# ESP32.net
KiCad netlist of a schematic drawn in Altium Designer
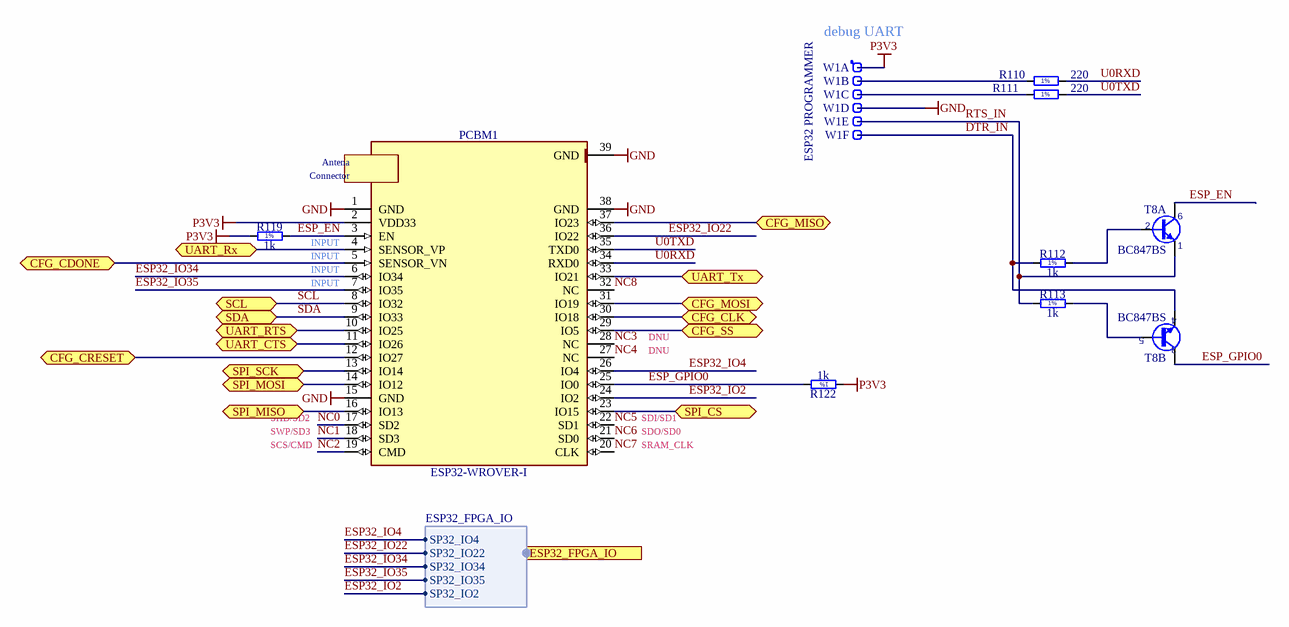
[diagram p0: ESP32.SchDoc]

(export (version "E")
  (design (tool "Eeschema 10.0.6"))
  (components
    (comp (ref "PCBM1")
      (value "ESP32-WROVER-I")
      (footprint "PCBM_ESP32-WROVER-I")
      (description "Generic WiFi-BT-BLE MCU Module")
      (fields
        (field (name "PART NUMBER") "PCBM_ESP32-WROVER-I")
        (field (name "MANUFACTURER") "ESPRESSIF")
        (field (name "AUTHOR") "CERN DEM JLC")
      )
      (libsource (lib "ICs And Semiconductors") (part "PCBM_ESP32-WROVER-I"))
    )
    (comp (ref "R110")
      (value "220")
      (footprint "RESC1005X40N")
      (description "Resistor - 1%")
      (fields
        (field (name "PART NUMBER") "R0402_220R_1%_0.0625W_100PPM")
        (field (name "POWER") "0.0625W")
        (field (name "AUTHOR") "CERN DEM JLC")
      )
      (libsource (lib "Resistors") (part "Resistor - 1%"))
    )
    (comp (ref "R111")
      (value "220")
      (footprint "RESC1005X40N")
      (description "Resistor - 1%")
      (fields
        (field (name "PART NUMBER") "R0402_220R_1%_0.0625W_100PPM")
        (field (name "POWER") "0.0625W")
        (field (name "AUTHOR") "CERN DEM JLC")
      )
      (libsource (lib "Resistors") (part "Resistor - 1%"))
    )
    (comp (ref "R112")
      (value "1k")
      (footprint "RESC1005X40N")
      (description "Resistor - 1%")
      (fields
        (field (name "PART NUMBER") "R0402_1K_1%_0.0625W_100PPM")
        (field (name "POWER") "0.0625W")
        (field (name "AUTHOR") "CERN DEM JLC")
      )
      (libsource (lib "Resistors") (part "Resistor - 1%"))
    )
    (comp (ref "R113")
      (value "1k")
      (footprint "RESC1005X40N")
      (description "Resistor - 1%")
      (fields
        (field (name "PART NUMBER") "R0402_1K_1%_0.0625W_100PPM")
        (field (name "POWER") "0.0625W")
        (field (name "AUTHOR") "CERN DEM JLC")
      )
      (libsource (lib "Resistors") (part "Resistor - 1%"))
    )
    (comp (ref "R119")
      (value "1k")
      (footprint "RESC1005X40N")
      (description "Resistor - 1%")
      (fields
        (field (name "PART NUMBER") "R0402_1K_1%_0.0625W_100PPM")
        (field (name "POWER") "0.0625W")
        (field (name "AUTHOR") "CERN DEM JLC")
      )
      (libsource (lib "Resistors") (part "Resistor - 1%"))
    )
    (comp (ref "R122")
      (value "1k")
      (footprint "RESC1005X40N")
      (description "Resistor - 1%")
      (fields
        (field (name "PART NUMBER") "R0402_1K_1%_0.0625W_100PPM")
        (field (name "POWER") "0.0625W")
        (field (name "AUTHOR") "CERN DEM JLC")
      )
      (libsource (lib "Resistors") (part "Resistor - 1%"))
    )
    (comp (ref "T8")
      (value "BC847BS")
      (footprint "SOT65P210X110-6N")
      (description "45V 100mA Dual NPN General-Purpose Transistor")
      (fields (field (name "MANUFACTURER") "NXP SEMICONDUCTORS") (field (name "AUTHOR") "CERN DEM JMW"))
      (libsource (lib "") (part "BC847BS_1"))
    )
    (comp (ref "W1")
      (value "Header 6")
      (footprint "SAMTEC_MTLW-106-07-L-S-250")
      (description "6 Mini Wire-Wrap Contact Strip Header")
      (fields
        (field (name "PART NUMBER") "SAMTEC_MTLW-106-07-L-S-250")
        (field (name "MANUFACTURER") "SAMTEC")
        (field (name "AUTHOR") "CERN DEM BC")
      )
      (libsource (lib "Connectors") (part "Wire-Wrap Contact x6"))
    )
  )
  (nets
    (net (code "2") (name "/CFG_CDONE") (class "Default")
      (node (ref "PCBM1") (pin "5") (pinfunction "SENSOR_VN_5") (pintype "input"))
    )
    (net (code "3") (name "/CFG_CLK") (class "Default")
      (node (ref "PCBM1") (pin "30") (pinfunction "IO18_30") (pintype "bidirectional"))
    )
    (net (code "4") (name "/CFG_CRESET") (class "Default")
      (node (ref "PCBM1") (pin "12") (pinfunction "IO27_12") (pintype "bidirectional"))
    )
    (net (code "5") (name "/CFG_MISO") (class "Default")
      (node (ref "PCBM1") (pin "37") (pinfunction "IO23_37") (pintype "bidirectional"))
    )
    (net (code "6") (name "/CFG_MOSI") (class "Default")
      (node (ref "PCBM1") (pin "31") (pinfunction "IO19_31") (pintype "bidirectional"))
    )
    (net (code "7") (name "/CFG_SS") (class "Default")
      (node (ref "PCBM1") (pin "29") (pinfunction "IO5_29") (pintype "bidirectional"))
    )
    (net (code "8") (name "/DTR_IN") (class "Default")
      (node (ref "R112") (pin "1") (pinfunction "1_1") (pintype "passive"))
      (node (ref "T8") (pin "4") (pinfunction "E_4") (pintype "passive"))
      (node (ref "W1") (pin "6") (pinfunction "6_6") (pintype "bidirectional"))
    )
    (net (code "9") (name "/ESP32_IO2") (class "Default")
      (node (ref "PCBM1") (pin "24") (pinfunction "IO2_24") (pintype "bidirectional"))
    )
    (net (code "10") (name "/ESP32_IO4") (class "Default")
      (node (ref "PCBM1") (pin "26") (pinfunction "IO4_26") (pintype "bidirectional"))
    )
    (net (code "11") (name "/ESP32_IO22") (class "Default")
      (node (ref "PCBM1") (pin "36") (pinfunction "IO22_36") (pintype "bidirectional"))
    )
    (net (code "12") (name "/ESP32_IO34") (class "Default")
      (node (ref "PCBM1") (pin "6") (pinfunction "IO34_6") (pintype "bidirectional"))
    )
    (net (code "13") (name "/ESP32_IO35") (class "Default")
      (node (ref "PCBM1") (pin "7") (pinfunction "IO35_7") (pintype "bidirectional"))
    )
    (net (code "14") (name "/ESP_EN") (class "Default")
      (node (ref "PCBM1") (pin "3") (pinfunction "EN_3") (pintype "input"))
      (node (ref "R119") (pin "2") (pinfunction "2_2") (pintype "passive"))
      (node (ref "T8") (pin "6") (pinfunction "C_6") (pintype "passive"))
    )
    (net (code "15") (name "/ESP_GPIO0") (class "Default")
      (node (ref "PCBM1") (pin "25") (pinfunction "IO0_25") (pintype "bidirectional"))
      (node (ref "R122") (pin "2") (pinfunction "2_2") (pintype "passive"))
      (node (ref "T8") (pin "3") (pinfunction "C_3") (pintype "passive"))
    )
    (net (code "16") (name "/NC0") (class "Default")
      (node (ref "PCBM1") (pin "17") (pinfunction "SD2_17") (pintype "bidirectional"))
    )
    (net (code "17") (name "/NC1") (class "Default")
      (node (ref "PCBM1") (pin "18") (pinfunction "SD3_18") (pintype "bidirectional"))
    )
    (net (code "18") (name "/NC2") (class "Default")
      (node (ref "PCBM1") (pin "19") (pinfunction "CMD_19") (pintype "bidirectional"))
    )
    (net (code "19") (name "/NC3") (class "Default")
      (node (ref "PCBM1") (pin "28") (pinfunction "NC_28") (pintype "passive"))
    )
    (net (code "20") (name "/NC4") (class "Default")
      (node (ref "PCBM1") (pin "27") (pinfunction "NC_27") (pintype "passive"))
    )
    (net (code "21") (name "/NC5") (class "Default")
      (node (ref "PCBM1") (pin "22") (pinfunction "SD1_22") (pintype "bidirectional"))
    )
    (net (code "22") (name "/NC6") (class "Default")
      (node (ref "PCBM1") (pin "21") (pinfunction "SD0_21") (pintype "bidirectional"))
    )
    (net (code "23") (name "/NC7") (class "Default")
      (node (ref "PCBM1") (pin "20") (pinfunction "CLK_20") (pintype "bidirectional"))
    )
    (net (code "24") (name "/NC8") (class "Default")
      (node (ref "PCBM1") (pin "32") (pinfunction "NC_32") (pintype "passive"))
    )
    (net (code "25") (name "/RTS_IN") (class "Default")
      (node (ref "R113") (pin "1") (pinfunction "1_1") (pintype "passive"))
      (node (ref "T8") (pin "1") (pinfunction "E_1") (pintype "passive"))
      (node (ref "W1") (pin "5") (pinfunction "5_5") (pintype "bidirectional"))
    )
    (net (code "26") (name "/SCL") (class "Default")
      (node (ref "PCBM1") (pin "8") (pinfunction "IO32_8") (pintype "bidirectional"))
    )
    (net (code "27") (name "/SDA") (class "Default")
      (node (ref "PCBM1") (pin "9") (pinfunction "IO33_9") (pintype "bidirectional"))
    )
    (net (code "28") (name "/SPI_CS") (class "Default")
      (node (ref "PCBM1") (pin "23") (pinfunction "IO15_23") (pintype "bidirectional"))
    )
    (net (code "29") (name "/SPI_MISO") (class "Default")
      (node (ref "PCBM1") (pin "16") (pinfunction "IO13_16") (pintype "bidirectional"))
    )
    (net (code "30") (name "/SPI_MOSI") (class "Default")
      (node (ref "PCBM1") (pin "14") (pinfunction "IO12_14") (pintype "bidirectional"))
    )
    (net (code "31") (name "/SPI_SCK") (class "Default")
      (node (ref "PCBM1") (pin "13") (pinfunction "IO14_13") (pintype "bidirectional"))
    )
    (net (code "32") (name "/U0RXD") (class "Default")
      (node (ref "PCBM1") (pin "34") (pinfunction "RXD0_34") (pintype "bidirectional"))
      (node (ref "R110") (pin "2") (pinfunction "2_2") (pintype "passive"))
    )
    (net (code "33") (name "/U0TXD") (class "Default")
      (node (ref "PCBM1") (pin "35") (pinfunction "TXD0_35") (pintype "bidirectional"))
      (node (ref "R111") (pin "2") (pinfunction "2_2") (pintype "passive"))
    )
    (net (code "34") (name "/UART_CTS") (class "Default")
      (node (ref "PCBM1") (pin "11") (pinfunction "IO26_11") (pintype "bidirectional"))
    )
    (net (code "35") (name "/UART_RTS") (class "Default")
      (node (ref "PCBM1") (pin "10") (pinfunction "IO25_10") (pintype "bidirectional"))
    )
    (net (code "36") (name "/UART_Rx") (class "Default")
      (node (ref "PCBM1") (pin "4") (pinfunction "SENSOR_VP_4") (pintype "input"))
    )
    (net (code "37") (name "/UART_Tx") (class "Default")
      (node (ref "PCBM1") (pin "33") (pinfunction "IO21_33") (pintype "bidirectional"))
    )
    (net (code "39") (name "GND") (class "Default")
      (node (ref "PCBM1") (pin "1") (pinfunction "GND_1") (pintype "power_in"))
      (node (ref "PCBM1") (pin "15") (pinfunction "GND_15") (pintype "power_in"))
      (node (ref "PCBM1") (pin "38") (pinfunction "GND_38") (pintype "power_in"))
      (node (ref "PCBM1") (pin "39") (pinfunction "GND_39") (pintype "power_in"))
      (node (ref "W1") (pin "4") (pinfunction "4_4") (pintype "bidirectional"))
    )
    (net (code "40") (name "Net-(R110-Pad1)") (class "Default")
      (node (ref "R110") (pin "1") (pinfunction "1_1") (pintype "passive"))
      (node (ref "W1") (pin "2") (pinfunction "2_2") (pintype "bidirectional"))
    )
    (net (code "41") (name "Net-(R111-Pad1)") (class "Default")
      (node (ref "R111") (pin "1") (pinfunction "1_1") (pintype "passive"))
      (node (ref "W1") (pin "3") (pinfunction "3_3") (pintype "bidirectional"))
    )
    (net (code "42") (name "Net-(T8A-B)") (class "Default")
      (node (ref "R112") (pin "2") (pinfunction "2_2") (pintype "passive"))
      (node (ref "T8") (pin "2") (pinfunction "B_2") (pintype "passive"))
    )
    (net (code "43") (name "Net-(T8B-B)") (class "Default")
      (node (ref "R113") (pin "2") (pinfunction "2_2") (pintype "passive"))
      (node (ref "T8") (pin "5") (pinfunction "B_5") (pintype "passive"))
    )
    (net (code "44") (name "P3V3") (class "Default")
      (node (ref "PCBM1") (pin "2") (pinfunction "VDD33_2") (pintype "power_in"))
      (node (ref "R119") (pin "1") (pinfunction "1_1") (pintype "passive"))
      (node (ref "R122") (pin "1") (pinfunction "1_1") (pintype "passive"))
      (node (ref "W1") (pin "1") (pinfunction "1_1") (pintype "bidirectional"))
    )
  )
)
